# LaserLider.net
KiCad netlist of a schematic drawn in Altium Designer
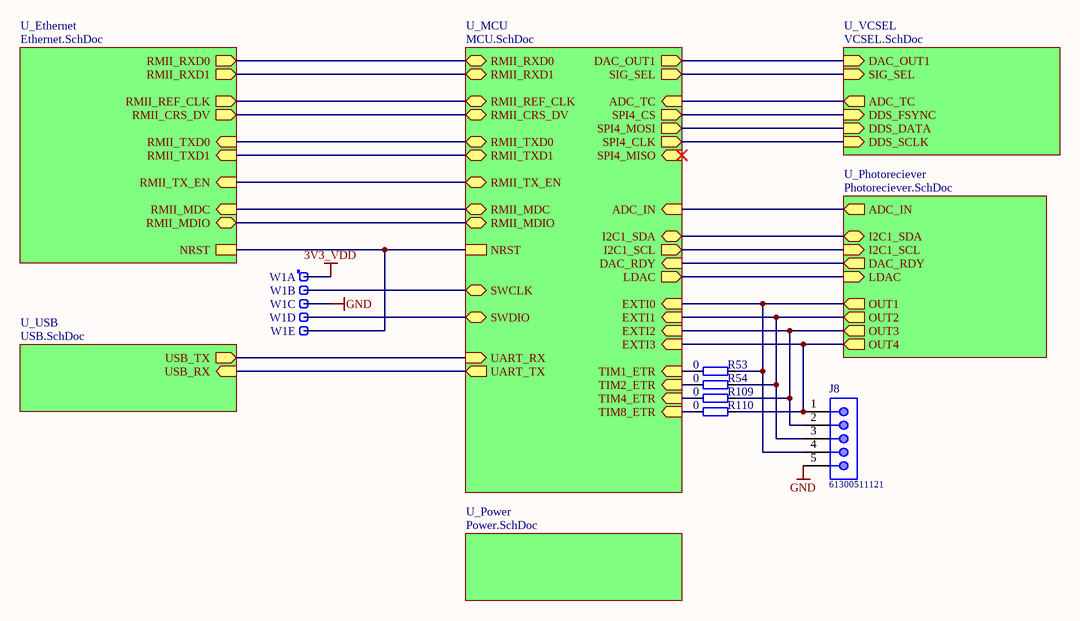
[diagram p0: LaserLider.SchDoc]

(export (version "E")
  (design (tool "Eeschema 10.0.6"))
  (components
    (comp (ref "J8")
      (value "61300511121")
      (footprint "61300511121")
      (description "WR-PHD Pin Header, THT, pitch 2.54mm, Single Row, Vertical, 5pin")
      (fields (field (name "PUBLISHER") "Wurth Elektronik"))
      (libsource (lib "ALTIUM-WR-PHD_PIN_HEADER_SOCKET_HEADER-rev19a") (part "61300511121"))
    )
    (comp (ref "R53")
      (value "0")
      (footprint "RESC1005X40N")
      (description "Resistor")
      (fields
        (field (name "PART NUMBER") "R0402_0R_JUMPER")
        (field (name "MANUFACTURER") "GENERIC")
        (field (name "AUTHOR") "CERN DEM JLC")
      )
      (libsource (lib "Resistors") (part "Resistor"))
    )
    (comp (ref "R54")
      (value "0")
      (footprint "RESC1005X40N")
      (description "Resistor")
      (fields
        (field (name "PART NUMBER") "R0402_0R_JUMPER")
        (field (name "MANUFACTURER") "GENERIC")
        (field (name "AUTHOR") "CERN DEM JLC")
      )
      (libsource (lib "Resistors") (part "Resistor"))
    )
    (comp (ref "R109")
      (value "0")
      (footprint "RESC1005X40N")
      (description "Resistor")
      (fields
        (field (name "PART NUMBER") "R0402_0R_JUMPER")
        (field (name "MANUFACTURER") "GENERIC")
        (field (name "AUTHOR") "CERN DEM JLC")
      )
      (libsource (lib "Resistors") (part "Resistor"))
    )
    (comp (ref "R110")
      (value "0")
      (footprint "RESC1005X40N")
      (description "Resistor")
      (fields
        (field (name "PART NUMBER") "R0402_0R_JUMPER")
        (field (name "MANUFACTURER") "GENERIC")
        (field (name "AUTHOR") "CERN DEM JLC")
      )
      (libsource (lib "Resistors") (part "Resistor"))
    )
    (comp (ref "W1")
      (value "Header 5")
      (footprint "SAMTEC_MTLW-105-07-L-S-250")
      (description "5 Mini Wire-Wrap Contact Strip Header")
      (fields
        (field (name "PART NUMBER") "SAMTEC_MTLW-105-07-L-S-250")
        (field (name "MANUFACTURER") "SAMTEC")
        (field (name "AUTHOR") "CERN DEM JLC")
      )
      (libsource (lib "Connectors") (part "Wire-Wrap Contact x5"))
    )
  )
  (nets
    (net (code "8") (name "/NRST") (class "Default")
      (node (ref "W1") (pin "5") (pinfunction "5_5") (pintype "bidirectional"))
    )
    (net (code "9") (name "/OUT1") (class "Default")
      (node (ref "J8") (pin "4") (pinfunction "4_4") (pintype "passive"))
      (node (ref "R53") (pin "2") (pinfunction "2_2") (pintype "passive"))
    )
    (net (code "10") (name "/OUT2") (class "Default")
      (node (ref "J8") (pin "3") (pinfunction "3_3") (pintype "passive"))
      (node (ref "R54") (pin "2") (pinfunction "2_2") (pintype "passive"))
    )
    (net (code "11") (name "/OUT3") (class "Default")
      (node (ref "J8") (pin "2") (pinfunction "2_2") (pintype "passive"))
      (node (ref "R109") (pin "2") (pinfunction "2_2") (pintype "passive"))
    )
    (net (code "12") (name "/OUT4") (class "Default")
      (node (ref "J8") (pin "1") (pinfunction "1_1") (pintype "passive"))
      (node (ref "R110") (pin "2") (pinfunction "2_2") (pintype "passive"))
    )
    (net (code "27") (name "/SWCLK") (class "Default")
      (node (ref "W1") (pin "2") (pinfunction "2_2") (pintype "bidirectional"))
    )
    (net (code "28") (name "/SWDIO") (class "Default")
      (node (ref "W1") (pin "4") (pinfunction "4_4") (pintype "bidirectional"))
    )
    (net (code "29") (name "/TIM1_ETR") (class "Default")
      (node (ref "R53") (pin "1") (pinfunction "1_1") (pintype "passive"))
    )
    (net (code "30") (name "/TIM2_ETR") (class "Default")
      (node (ref "R54") (pin "1") (pinfunction "1_1") (pintype "passive"))
    )
    (net (code "31") (name "/TIM4_ETR") (class "Default")
      (node (ref "R109") (pin "1") (pinfunction "1_1") (pintype "passive"))
    )
    (net (code "32") (name "/TIM8_ETR") (class "Default")
      (node (ref "R110") (pin "1") (pinfunction "1_1") (pintype "passive"))
    )
    (net (code "35") (name "3V3_VDD") (class "Default")
      (node (ref "W1") (pin "1") (pinfunction "1_1") (pintype "bidirectional"))
    )
    (net (code "36") (name "GND") (class "Default")
      (node (ref "J8") (pin "5") (pinfunction "5_5") (pintype "passive"))
      (node (ref "W1") (pin "3") (pinfunction "3_3") (pintype "bidirectional"))
    )
  )
)
